# TK513_Limiter.net
KiCad netlist of a schematic drawn in Altium Designer
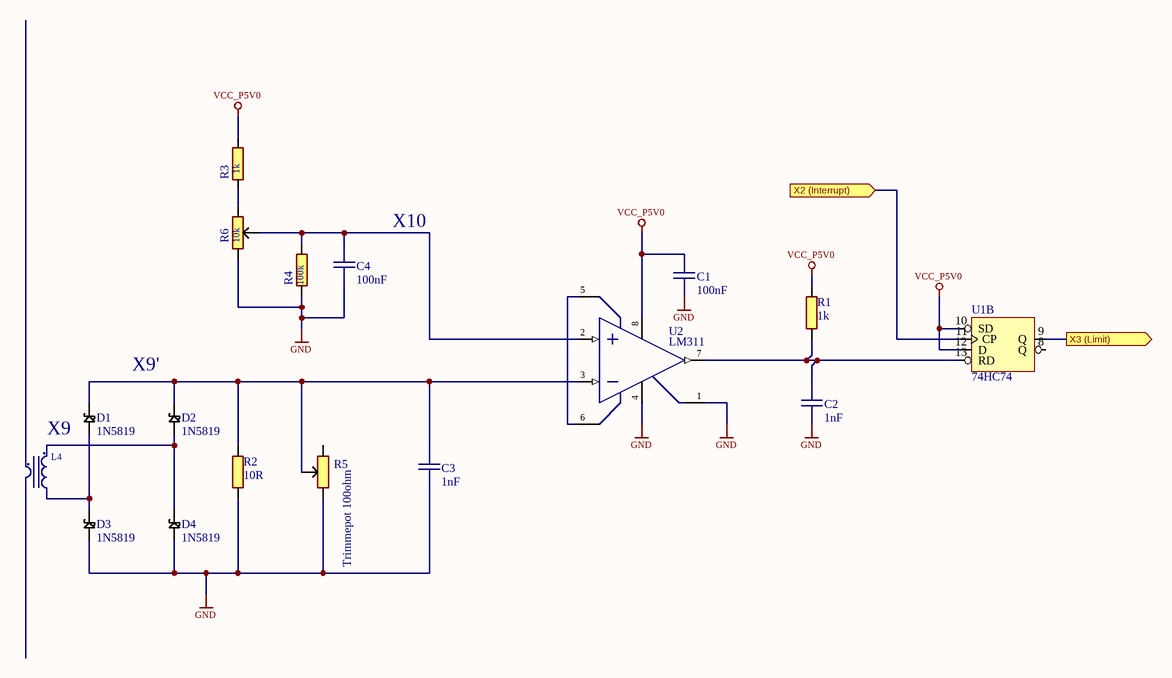
[diagram p0: TK513_Limiter.SchDoc]

(export (version "E")
  (design (tool "Eeschema 10.0.6"))
  (components
    (comp (ref "C1")
      (value "100nF")
      (footprint "CAPC0603(1608)55_N")
      (description "X7R 50V 5%")
      (libsource (lib "OVLib") (part "CAP"))
    )
    (comp (ref "C2")
      (value "1nF")
      (footprint "CAPC0603(1608)55_N")
      (description "X7R 50V 5%")
      (libsource (lib "OVLib") (part "CAP"))
    )
    (comp (ref "C3")
      (value "1nF")
      (footprint "CAPC0603(1608)55_N")
      (description "X7R 50V 5%")
      (libsource (lib "OVLib") (part "CAP"))
    )
    (comp (ref "C4")
      (value "100nF")
      (footprint "CAPC0603(1608)55_N")
      (description "X7R 50V 5%")
      (libsource (lib "OVLib") (part "CAP"))
    )
    (comp (ref "D1") (value "1N5819") (footprint "DO-41") (libsource (lib "OVLib") (part "SchottkyDiode")))
    (comp (ref "D2") (value "1N5819") (footprint "DO-41") (libsource (lib "OVLib") (part "SchottkyDiode")))
    (comp (ref "D3") (value "1N5819") (footprint "DO-41") (libsource (lib "OVLib") (part "SchottkyDiode")))
    (comp (ref "D4") (value "1N5819") (footprint "DO-41") (libsource (lib "OVLib") (part "SchottkyDiode")))
    (comp (ref "L4")
      (value "CurrentSenseTransformer")
      (libsource (lib "OVLib") (part "Current_sensing_transformer"))
    )
    (comp (ref "R1")
      (value "1k")
      (footprint "RESC0603(1608)_N")
      (description "0.1W 1% Thick film resistor")
      (libsource (lib "OVLib") (part "Resistor2"))
    )
    (comp (ref "R2")
      (value "10R")
      (footprint "RESC0805(2012)_N")
      (description "0.1W 1% Thick film resistor")
      (libsource (lib "OVLib") (part "Resistor2"))
    )
    (comp (ref "R3")
      (value "1k")
      (footprint "RESC0603(1608)_N")
      (description "0.1W 1% Thick film resistor")
      (libsource (lib "OVLib") (part "Resistor2"))
    )
    (comp (ref "R4")
      (value "100k")
      (footprint "RESC0603(1608)_N")
      (description "0.1W 1% Thick film resistor")
      (libsource (lib "OVLib") (part "Resistor2"))
    )
    (comp (ref "R5")
      (value "Trimmepot 100ohm")
      (footprint "TRIMPOT_3006P")
      (description "15 turn, horizontal")
      (libsource (lib "") (part "Potmeter_1"))
    )
    (comp (ref "R6")
      (value "Trimmepot 10kohm")
      (footprint "TRIMPOT_3006P")
      (description "15 turn, horizontal")
      (libsource (lib "OVLib") (part "Potmeter"))
    )
    (comp (ref "U1") (value "74HC74") (footprint "SOIC-14") (libsource (lib "OVLib") (part "2XD-Flip-Flop")))
    (comp (ref "U2")
      (value "LM311")
      (footprint "SOIC-8-WIDE")
      (description "Comparator, High Speed")
      (libsource (lib "OVLib") (part "Comparator_Complex"))
    )
  )
  (nets
    (net (code "1") (name "/X2 (Interrupt)") (class "Default")
      (node (ref "U1") (pin "11") (pinfunction "CP_11") (pintype "passive"))
    )
    (net (code "2") (name "/X3 (Limit)") (class "Default")
      (node (ref "U1") (pin "9") (pinfunction "Q_9") (pintype "passive"))
    )
    (net (code "3") (name "GND") (class "Default")
      (node (ref "C1") (pin "1") (pinfunction "1_1") (pintype "passive"))
      (node (ref "C2") (pin "1") (pinfunction "1_1") (pintype "passive"))
      (node (ref "C3") (pin "1") (pinfunction "1_1") (pintype "passive"))
      (node (ref "C4") (pin "1") (pinfunction "1_1") (pintype "passive"))
      (node (ref "D3") (pin "1") (pinfunction "A_1") (pintype "passive"))
      (node (ref "D4") (pin "1") (pinfunction "A_1") (pintype "passive"))
      (node (ref "R2") (pin "2") (pinfunction "2_2") (pintype "passive"))
      (node (ref "R4") (pin "2") (pinfunction "2_2") (pintype "passive"))
      (node (ref "R5") (pin "1") (pinfunction "1_1") (pintype "passive"))
      (node (ref "R6") (pin "3") (pinfunction "3_3") (pintype "passive"))
      (node (ref "U2") (pin "1") (pinfunction "GND_1") (pintype "power_in"))
      (node (ref "U2") (pin "4") (pinfunction "V-_4") (pintype "power_in"))
    )
    (net (code "4") (name "Net-(D1-A)") (class "Default")
      (node (ref "D1") (pin "1") (pinfunction "A_1") (pintype "passive"))
      (node (ref "D3") (pin "2") (pinfunction "K_2") (pintype "passive"))
      (node (ref "L4") (pin "3") (pinfunction "3_3") (pintype "passive"))
    )
    (net (code "5") (name "Net-(D1-K)") (class "Default")
      (node (ref "C3") (pin "2") (pinfunction "2_2") (pintype "passive"))
      (node (ref "D1") (pin "2") (pinfunction "K_2") (pintype "passive"))
      (node (ref "D2") (pin "2") (pinfunction "K_2") (pintype "passive"))
      (node (ref "R2") (pin "1") (pinfunction "1_1") (pintype "passive"))
      (node (ref "R5") (pin "2") (pinfunction "2_2") (pintype "passive"))
      (node (ref "U2") (pin "3") (pinfunction "IN-_3") (pintype "input"))
    )
    (net (code "6") (name "Net-(D2-A)") (class "Default")
      (node (ref "D2") (pin "1") (pinfunction "A_1") (pintype "passive"))
      (node (ref "D4") (pin "2") (pinfunction "K_2") (pintype "passive"))
      (node (ref "L4") (pin "4") (pinfunction "4_4") (pintype "passive"))
    )
    (net (code "7") (name "Net-(R3-Pad2)") (class "Default")
      (node (ref "R3") (pin "2") (pinfunction "2_2") (pintype "passive"))
      (node (ref "R6") (pin "1") (pinfunction "1_1") (pintype "passive"))
    )
    (net (code "8") (name "Net-(U1B-RD)") (class "Default")
      (node (ref "C2") (pin "2") (pinfunction "2_2") (pintype "passive"))
      (node (ref "R1") (pin "2") (pinfunction "2_2") (pintype "passive"))
      (node (ref "U1") (pin "13") (pinfunction "RD_13") (pintype "passive"))
      (node (ref "U2") (pin "7") (pinfunction "OUT_7") (pintype "output"))
    )
    (net (code "9") (name "Net-(U2-BAL)") (class "Default")
      (node (ref "U2") (pin "5") (pinfunction "BAL_5") (pintype "passive"))
      (node (ref "U2") (pin "6") (pinfunction "BAL/STB_6") (pintype "passive"))
    )
    (net (code "10") (name "Net-(U2-IN+)") (class "Default")
      (node (ref "C4") (pin "2") (pinfunction "2_2") (pintype "passive"))
      (node (ref "R4") (pin "1") (pinfunction "1_1") (pintype "passive"))
      (node (ref "R6") (pin "2") (pinfunction "2_2") (pintype "passive"))
      (node (ref "U2") (pin "2") (pinfunction "IN+_2") (pintype "input"))
    )
    (net (code "11") (name "VCC_P5V0") (class "Default")
      (node (ref "C1") (pin "2") (pinfunction "2_2") (pintype "passive"))
      (node (ref "R1") (pin "1") (pinfunction "1_1") (pintype "passive"))
      (node (ref "R3") (pin "1") (pinfunction "1_1") (pintype "passive"))
      (node (ref "U1") (pin "10") (pinfunction "SD_10") (pintype "passive"))
      (node (ref "U1") (pin "12") (pinfunction "D_12") (pintype "passive"))
      (node (ref "U2") (pin "8") (pinfunction "V+_8") (pintype "power_in"))
    )
    (net (code "12") (name "unconnected-(L4-Pad1)") (class "Default")
      (node (ref "L4") (pin "1") (pinfunction "1_1") (pintype "passive"))
    )
    (net (code "13") (name "unconnected-(L4-Pad2)") (class "Default")
      (node (ref "L4") (pin "2") (pinfunction "2_2") (pintype "passive"))
    )
    (net (code "14") (name "unconnected-(R5-Pad3)") (class "Default")
      (node (ref "R5") (pin "3") (pinfunction "3_3") (pintype "passive"))
    )
    (net (code "15") (name "unconnected-(U1B-Q-Pad8)") (class "Default")
      (node (ref "U1") (pin "8") (pinfunction "Q_8") (pintype "passive"))
    )
  )
)
